# DA14580_QFN40.net
KiCad netlist of a schematic drawn in EAGLE
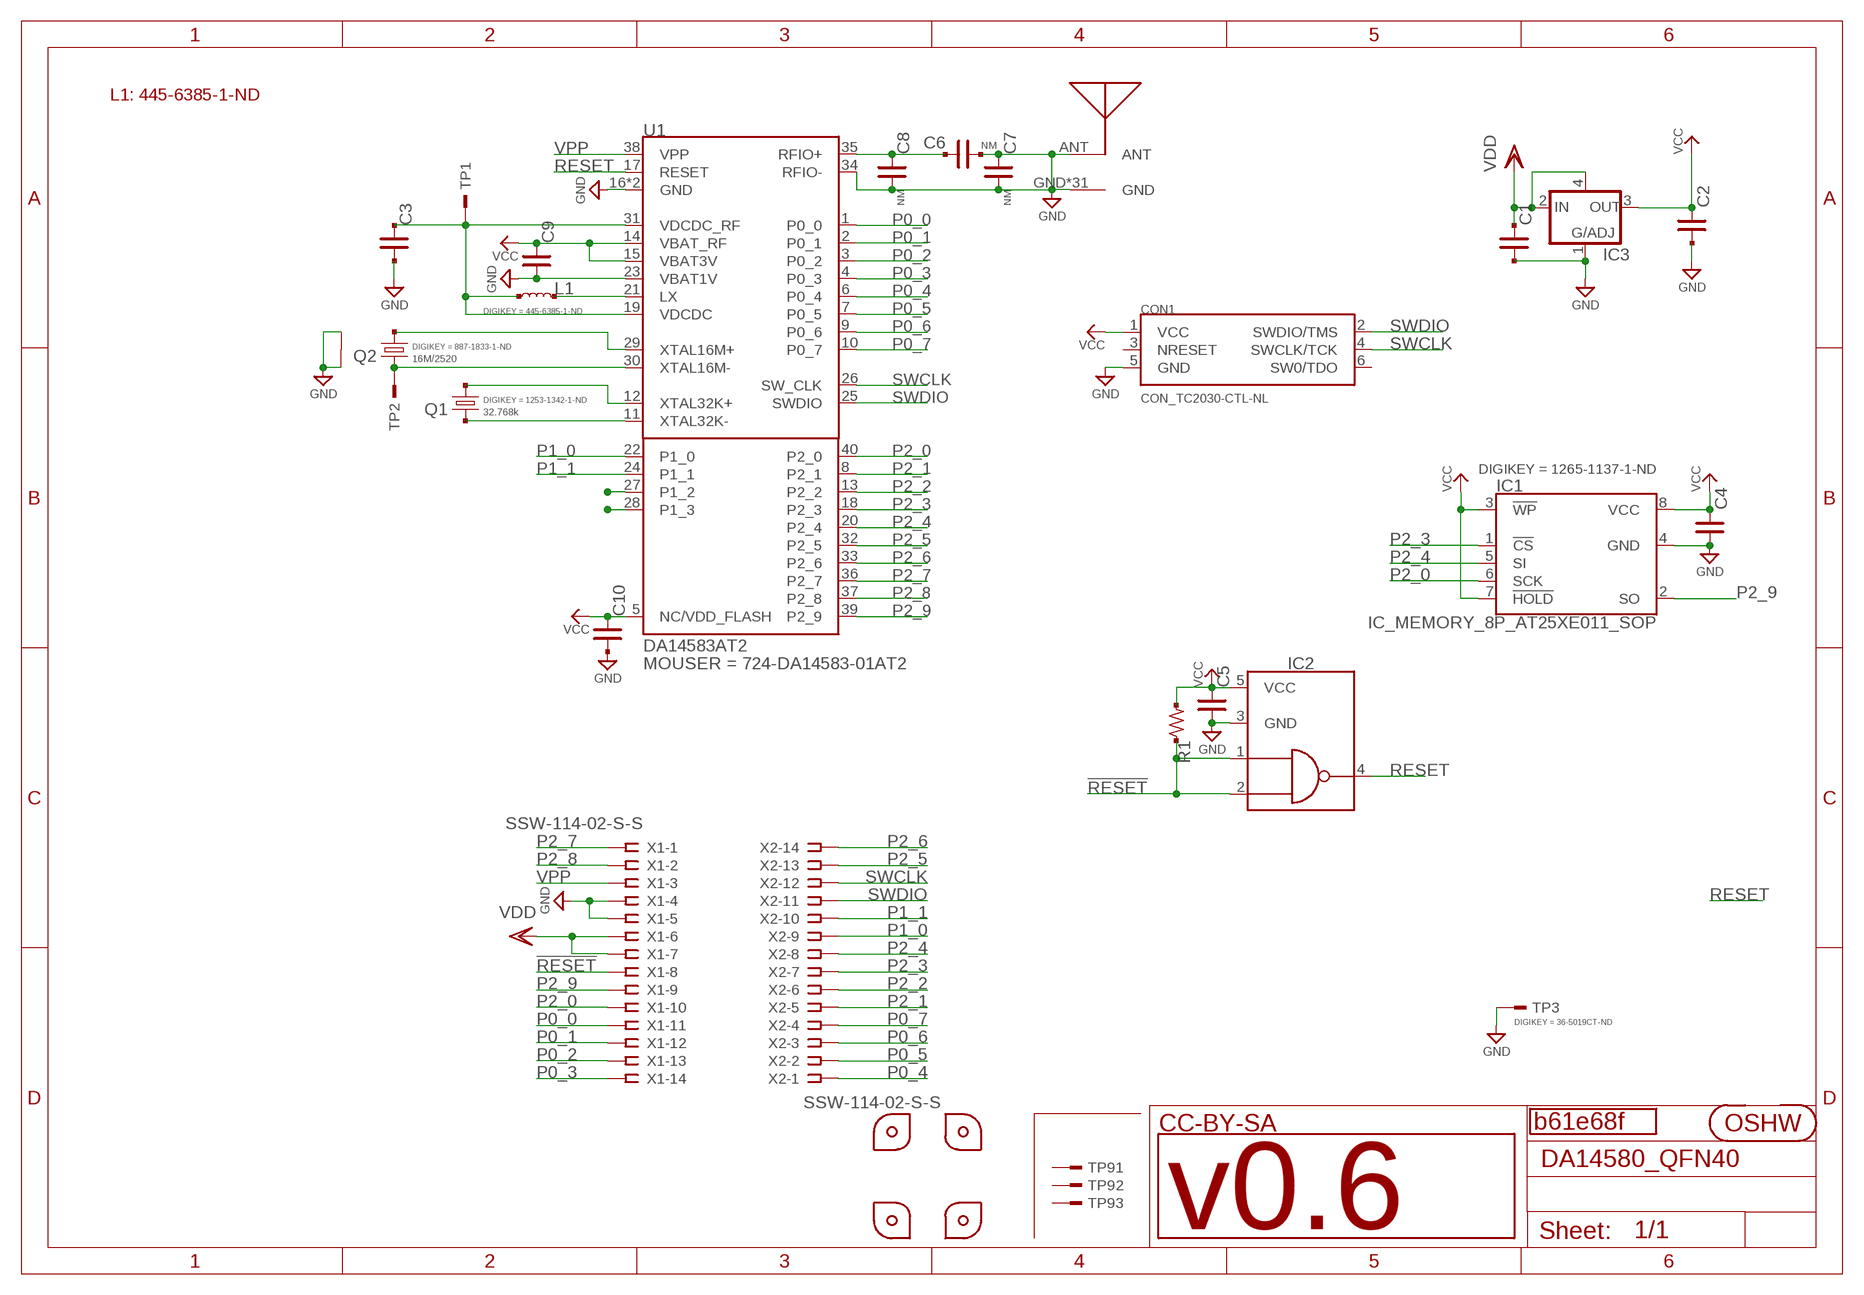
[diagram p0: schematic, sheet 1]

(export (version "E")
  (design (tool "Eeschema 10.0.6"))
  (components
    (comp (ref "C1")
      (value "C_SMD_1.0U_1005")
      (footprint "eagle-import:C0402")
      (libsource (lib "eagle-import") (part "C_SMD__10051.0U"))
    )
    (comp (ref "C2")
      (value "C_SMD_1.0U_1005")
      (footprint "eagle-import:C0402")
      (libsource (lib "eagle-import") (part "C_SMD__10051.0U"))
    )
    (comp (ref "C3")
      (value "C_SMD_1.0U_1005")
      (footprint "eagle-import:C0402")
      (libsource (lib "eagle-import") (part "C_SMD__10051.0U"))
    )
    (comp (ref "C4")
      (value "C_SMD_0.1U_1005")
      (footprint "eagle-import:C0402")
      (libsource (lib "eagle-import") (part "C_SMD__10050.1U"))
    )
    (comp (ref "C5")
      (value "C_SMD_0.1U_1005")
      (footprint "eagle-import:C0402")
      (libsource (lib "eagle-import") (part "C_SMD__10050.1U"))
    )
    (comp (ref "C6")
      (value "NM")
      (footprint "eagle-import:C0402")
      (libsource (lib "eagle-import") (part "C_SMD__100510P"))
    )
    (comp (ref "C7")
      (value "NM")
      (footprint "eagle-import:C0402")
      (libsource (lib "eagle-import") (part "C_SMD__1005"))
    )
    (comp (ref "C8")
      (value "NM")
      (footprint "eagle-import:C0402")
      (libsource (lib "eagle-import") (part "C_SMD__1005"))
    )
    (comp (ref "C9")
      (value "C_SMD_1.0U_1005")
      (footprint "eagle-import:C0402")
      (libsource (lib "eagle-import") (part "C_SMD__10051.0U"))
    )
    (comp (ref "C10")
      (value "C_SMD_0.1U_1005")
      (footprint "eagle-import:C0402")
      (libsource (lib "eagle-import") (part "C_SMD__10050.1U"))
    )
    (comp (ref "CON1")
      (value "CON_TC2030-CTL-NL")
      (footprint "eagle-import:CON_TC2030-IDC-NL")
      (libsource (lib "eagle-import") (part "CON_TC2030-CTL-NL"))
    )
    (comp (ref "GIT1")
      (value "b61e68f")
      (footprint "eagle-import:GIT-REVISION")
      (libsource (lib "eagle-import") (part "GIT-REVISION"))
    )
    (comp (ref "IC1")
      (value "IC_MEMORY_8P_AT25XE011_SOP")
      (footprint "eagle-import:IC_08_1.27_150MIL")
      (fields (field (name "DIGIKEY") "1265-1137-1-ND"))
      (libsource (lib "eagle-import") (part "IC_MEMORY_8P__SOPAT25XE011"))
    )
    (comp (ref "IC2")
      (value "74LVC1G00_DRL")
      (footprint "eagle-import:SOT50P160X120-5N")
      (libsource (lib "eagle-import") (part "741G00_DRLLVC"))
    )
    (comp (ref "IC3")
      (value "LDO4_3.3_SC82-AB")
      (footprint "eagle-import:SOT130P220X135-4N")
      (libsource (lib "eagle-import") (part "LDO4__SC82-AB3.3"))
    )
    (comp (ref "ICON1")
      (value "v0.6")
      (footprint "eagle-import:ICON_REVISION1.2")
      (libsource (lib "eagle-import") (part "ICON_REVISION_1.2"))
    )
    (comp (ref "L1")
      (value "INDUCTOR_2.2U_1608")
      (footprint "eagle-import:L_1608")
      (fields (field (name "DIGIKEY") "445-6385-1-ND"))
      (libsource (lib "eagle-import") (part "INDUCTOR__16082.2U"))
    )
    (comp (ref "P1")
      (value "PCB_CORNER_NH")
      (footprint "eagle-import:PCB_CORNER_NH")
      (libsource (lib "eagle-import") (part "PCB_CORNER_NH"))
    )
    (comp (ref "P2")
      (value "PCB_CORNER_NH")
      (footprint "eagle-import:PCB_CORNER_NH")
      (libsource (lib "eagle-import") (part "PCB_CORNER_NH"))
    )
    (comp (ref "P3")
      (value "PCB_CORNER")
      (footprint "eagle-import:PCB_CORNER")
      (libsource (lib "eagle-import") (part "PCB_CORNER"))
    )
    (comp (ref "P4")
      (value "PCB_CORNER")
      (footprint "eagle-import:PCB_CORNER")
      (libsource (lib "eagle-import") (part "PCB_CORNER"))
    )
    (comp (ref "Q1")
      (value "32.768k")
      (footprint "eagle-import:CR_2125")
      (fields (field (name "DIGIKEY") "1253-1342-1-ND"))
      (libsource (lib "eagle-import") (part "CRYSTAL2__201232.768K"))
    )
    (comp (ref "Q2")
      (value "16M/2520")
      (footprint "eagle-import:CLOCK_2520")
      (fields (field (name "DIGIKEY") "887-1833-1-ND"))
      (libsource (lib "eagle-import") (part "CRYSTAL4__252016M"))
    )
    (comp (ref "R1")
      (value "R_US_10K_1005")
      (footprint "eagle-import:C0402")
      (libsource (lib "eagle-import") (part "R_US__100510K"))
    )
    (comp (ref "TP1")
      (value "TESTPAD")
      (footprint "eagle-import:TP06RECT")
      (libsource (lib "eagle-import") (part "TESTPAD"))
    )
    (comp (ref "TP2")
      (value "TESTPAD")
      (footprint "eagle-import:TP06RECT")
      (libsource (lib "eagle-import") (part "TESTPAD"))
    )
    (comp (ref "TP3")
      (value "TESTPAD_4020")
      (footprint "eagle-import:TP_4020")
      (fields (field (name "DIGIKEY") "36-5019CT-ND"))
      (libsource (lib "eagle-import") (part "TESTPAD_4020"))
    )
    (comp (ref "TP91")
      (value "TESTPAD_F")
      (footprint "eagle-import:FIDUCIAL")
      (libsource (lib "eagle-import") (part "TESTPAD_F"))
    )
    (comp (ref "TP92")
      (value "TESTPAD_F")
      (footprint "eagle-import:FIDUCIAL")
      (libsource (lib "eagle-import") (part "TESTPAD_F"))
    )
    (comp (ref "TP93")
      (value "TESTPAD_F")
      (footprint "eagle-import:FIDUCIAL")
      (libsource (lib "eagle-import") (part "TESTPAD_F"))
    )
    (comp (ref "U$1")
      (value "ANT_IFA")
      (footprint "eagle-import:ANT_IFA_V2")
      (libsource (lib "eagle-import") (part "ANT_IFA"))
    )
    (comp (ref "U$2")
      (value "ICON_OSHW")
      (footprint "eagle-import:ICON_OSHW")
      (libsource (lib "eagle-import") (part "ICON_OSHW"))
    )
    (comp (ref "U1")
      (value "DA14583AT2")
      (footprint "eagle-import:QFN40_0.4P5.0X5.0")
      (fields (field (name "MOUSER") "724-DA14583-01AT2"))
      (libsource (lib "eagle-import") (part "DA1458AT23"))
    )
    (comp (ref "X1")
      (value "SSW-114-02-S-S")
      (footprint "eagle-import:SSW-114-02-S-S")
      (libsource (lib "eagle-import") (part "SSW-114-02-S-S"))
    )
    (comp (ref "X2")
      (value "SSW-114-02-S-S")
      (footprint "eagle-import:SSW-114-02-S-S")
      (libsource (lib "eagle-import") (part "SSW-114-02-S-S"))
    )
  )
  (nets
    (net (code "1") (name "/P0_0") (class "Default")
      (node (ref "U1") (pin "1") (pinfunction "P0_0_1") (pintype "bidirectional"))
      (node (ref "X1") (pin "11") (pinfunction "1_11") (pintype "passive"))
    )
    (net (code "2") (name "/P0_1") (class "Default")
      (node (ref "U1") (pin "2") (pinfunction "P0_1_2") (pintype "bidirectional"))
      (node (ref "X1") (pin "12") (pinfunction "1_12") (pintype "passive"))
    )
    (net (code "3") (name "/P0_2") (class "Default")
      (node (ref "U1") (pin "3") (pinfunction "P0_2_3") (pintype "bidirectional"))
      (node (ref "X1") (pin "13") (pinfunction "1_13") (pintype "passive"))
    )
    (net (code "4") (name "/P0_3") (class "Default")
      (node (ref "U1") (pin "4") (pinfunction "P0_3_4") (pintype "bidirectional"))
      (node (ref "X1") (pin "14") (pinfunction "1_14") (pintype "passive"))
    )
    (net (code "5") (name "/P0_4") (class "Default")
      (node (ref "U1") (pin "6") (pinfunction "P0_4_6") (pintype "bidirectional"))
      (node (ref "X2") (pin "1") (pinfunction "1_1") (pintype "passive"))
    )
    (net (code "6") (name "/P0_5") (class "Default")
      (node (ref "U1") (pin "7") (pinfunction "P0_5_7") (pintype "bidirectional"))
      (node (ref "X2") (pin "2") (pinfunction "1_2") (pintype "passive"))
    )
    (net (code "7") (name "/P0_6") (class "Default")
      (node (ref "U1") (pin "9") (pinfunction "P0_6_9") (pintype "bidirectional"))
      (node (ref "X2") (pin "3") (pinfunction "1_3") (pintype "passive"))
    )
    (net (code "8") (name "/P0_7") (class "Default")
      (node (ref "U1") (pin "10") (pinfunction "P0_7_10") (pintype "bidirectional"))
      (node (ref "X2") (pin "4") (pinfunction "1_4") (pintype "passive"))
    )
    (net (code "9") (name "/P1_0") (class "Default")
      (node (ref "U1") (pin "22") (pinfunction "P1_0_22") (pintype "bidirectional"))
      (node (ref "X2") (pin "9") (pinfunction "1_9") (pintype "passive"))
    )
    (net (code "10") (name "/P1_1") (class "Default")
      (node (ref "U1") (pin "24") (pinfunction "P1_1_24") (pintype "bidirectional"))
      (node (ref "X2") (pin "10") (pinfunction "1_10") (pintype "passive"))
    )
    (net (code "11") (name "/P2_0") (class "Default")
      (node (ref "IC1") (pin "6") (pinfunction "SCK_6") (pintype "input"))
      (node (ref "U1") (pin "40") (pinfunction "P2_0_40") (pintype "bidirectional"))
      (node (ref "X1") (pin "10") (pinfunction "1_10") (pintype "passive"))
    )
    (net (code "12") (name "/P2_1") (class "Default")
      (node (ref "U1") (pin "8") (pinfunction "P2_1_8") (pintype "bidirectional"))
      (node (ref "X2") (pin "5") (pinfunction "1_5") (pintype "passive"))
    )
    (net (code "13") (name "/P2_2") (class "Default")
      (node (ref "U1") (pin "13") (pinfunction "P2_2_13") (pintype "bidirectional"))
      (node (ref "X2") (pin "6") (pinfunction "1_6") (pintype "passive"))
    )
    (net (code "14") (name "/P2_3") (class "Default")
      (node (ref "IC1") (pin "1") (pinfunction "~{CS}_1") (pintype "input"))
      (node (ref "U1") (pin "18") (pinfunction "P2_3_18") (pintype "bidirectional"))
      (node (ref "X2") (pin "7") (pinfunction "1_7") (pintype "passive"))
    )
    (net (code "15") (name "/P2_4") (class "Default")
      (node (ref "IC1") (pin "5") (pinfunction "SI_5") (pintype "input"))
      (node (ref "U1") (pin "20") (pinfunction "P2_4_20") (pintype "bidirectional"))
      (node (ref "X2") (pin "8") (pinfunction "1_8") (pintype "passive"))
    )
    (net (code "16") (name "/P2_5") (class "Default")
      (node (ref "U1") (pin "32") (pinfunction "P2_5_32") (pintype "bidirectional"))
      (node (ref "X2") (pin "13") (pinfunction "1_13") (pintype "passive"))
    )
    (net (code "17") (name "/P2_6") (class "Default")
      (node (ref "U1") (pin "33") (pinfunction "P2_6_33") (pintype "bidirectional"))
      (node (ref "X2") (pin "14") (pinfunction "1_14") (pintype "passive"))
    )
    (net (code "18") (name "/P2_7") (class "Default")
      (node (ref "U1") (pin "36") (pinfunction "P2_7_36") (pintype "bidirectional"))
      (node (ref "X1") (pin "1") (pinfunction "1_1") (pintype "passive"))
    )
    (net (code "19") (name "/P2_8") (class "Default")
      (node (ref "U1") (pin "37") (pinfunction "P2_8_37") (pintype "bidirectional"))
      (node (ref "X1") (pin "2") (pinfunction "1_2") (pintype "passive"))
    )
    (net (code "20") (name "/P2_9") (class "Default")
      (node (ref "IC1") (pin "2") (pinfunction "SO_2") (pintype "output"))
      (node (ref "U1") (pin "39") (pinfunction "P2_9_39") (pintype "bidirectional"))
      (node (ref "X1") (pin "9") (pinfunction "1_9") (pintype "passive"))
    )
    (net (code "21") (name "/RESET") (class "Default")
      (node (ref "IC2") (pin "4") (pinfunction "1Y_4") (pintype "output"))
      (node (ref "U1") (pin "17") (pinfunction "RESET_17") (pintype "bidirectional"))
    )
    (net (code "22") (name "/SWCLK") (class "Default")
      (node (ref "CON1") (pin "4") (pinfunction "SWCLK/TCK_4") (pintype "bidirectional"))
      (node (ref "U1") (pin "26") (pinfunction "SW_CLK_26") (pintype "bidirectional"))
      (node (ref "X2") (pin "12") (pinfunction "1_12") (pintype "passive"))
    )
    (net (code "23") (name "/SWDIO") (class "Default")
      (node (ref "CON1") (pin "2") (pinfunction "SWDIO/TMS_2") (pintype "bidirectional"))
      (node (ref "U1") (pin "25") (pinfunction "SWDIO_25") (pintype "bidirectional"))
      (node (ref "X2") (pin "11") (pinfunction "1_11") (pintype "passive"))
    )
    (net (code "24") (name "/VPP") (class "Default")
      (node (ref "U1") (pin "38") (pinfunction "VPP_38") (pintype "power_in"))
      (node (ref "X1") (pin "3") (pinfunction "1_3") (pintype "passive"))
    )
    (net (code "25") (name "/~{RESET}") (class "Default")
      (node (ref "IC2") (pin "1") (pinfunction "1A_1") (pintype "input"))
      (node (ref "IC2") (pin "2") (pinfunction "1B_2") (pintype "input"))
      (node (ref "R1") (pin "1") (pinfunction "1_1") (pintype "passive"))
      (node (ref "X1") (pin "8") (pinfunction "1_8") (pintype "passive"))
    )
    (net (code "26") (name "GND") (class "Default")
      (node (ref "C1") (pin "2") (pinfunction "2_2") (pintype "passive"))
      (node (ref "C10") (pin "2") (pinfunction "2_2") (pintype "passive"))
      (node (ref "C2") (pin "2") (pinfunction "2_2") (pintype "passive"))
      (node (ref "C3") (pin "2") (pinfunction "2_2") (pintype "passive"))
      (node (ref "C4") (pin "2") (pinfunction "2_2") (pintype "passive"))
      (node (ref "C5") (pin "2") (pinfunction "2_2") (pintype "passive"))
      (node (ref "C6") (pin "2") (pinfunction "2_2") (pintype "passive"))
      (node (ref "C7") (pin "1") (pinfunction "1_1") (pintype "passive"))
      (node (ref "C7") (pin "2") (pinfunction "2_2") (pintype "passive"))
      (node (ref "C8") (pin "2") (pinfunction "2_2") (pintype "passive"))
      (node (ref "C9") (pin "2") (pinfunction "2_2") (pintype "passive"))
      (node (ref "CON1") (pin "5") (pinfunction "GND_5") (pintype "bidirectional"))
      (node (ref "IC1") (pin "4") (pinfunction "GND_4") (pintype "power_in"))
      (node (ref "IC2") (pin "3") (pinfunction "GND_3") (pintype "power_in"))
      (node (ref "IC3") (pin "1") (pinfunction "ADJ_1") (pintype "power_in"))
      (node (ref "Q2") (pin "2") (pinfunction "P$1_2") (pintype "bidirectional"))
      (node (ref "Q2") (pin "4") (pinfunction "P$2_4") (pintype "bidirectional"))
      (node (ref "TP3") (pin "TP") (pinfunction "1_TP") (pintype "passive"))
      (node (ref "U$1") (pin "ANT") (pinfunction "ANT_ANT") (pintype "bidirectional"))
      (node (ref "U$1") (pin "GND") (pinfunction "GND_GND") (pintype "bidirectional"))
      (node (ref "U$1") (pin "GND@1") (pinfunction "GND_GND@1") (pintype "bidirectional"))
      (node (ref "U$1") (pin "GND@10") (pinfunction "GND_GND@10") (pintype "bidirectional"))
      (node (ref "U$1") (pin "GND@11") (pinfunction "GND_GND@11") (pintype "bidirectional"))
      (node (ref "U$1") (pin "GND@12") (pinfunction "GND_GND@12") (pintype "bidirectional"))
      (node (ref "U$1") (pin "GND@13") (pinfunction "GND_GND@13") (pintype "bidirectional"))
      (node (ref "U$1") (pin "GND@14") (pinfunction "GND_GND@14") (pintype "bidirectional"))
      (node (ref "U$1") (pin "GND@15") (pinfunction "GND_GND@15") (pintype "bidirectional"))
      (node (ref "U$1") (pin "GND@16") (pinfunction "GND_GND@16") (pintype "bidirectional"))
      (node (ref "U$1") (pin "GND@17") (pinfunction "GND_GND@17") (pintype "bidirectional"))
      (node (ref "U$1") (pin "GND@18") (pinfunction "GND_GND@18") (pintype "bidirectional"))
      (node (ref "U$1") (pin "GND@19") (pinfunction "GND_GND@19") (pintype "bidirectional"))
      (node (ref "U$1") (pin "GND@2") (pinfunction "GND_GND@2") (pintype "bidirectional"))
      (node (ref "U$1") (pin "GND@20") (pinfunction "GND_GND@20") (pintype "bidirectional"))
      (node (ref "U$1") (pin "GND@21") (pinfunction "GND_GND@21") (pintype "bidirectional"))
      (node (ref "U$1") (pin "GND@22") (pinfunction "GND_GND@22") (pintype "bidirectional"))
      (node (ref "U$1") (pin "GND@23") (pinfunction "GND_GND@23") (pintype "bidirectional"))
      (node (ref "U$1") (pin "GND@24") (pinfunction "GND_GND@24") (pintype "bidirectional"))
      (node (ref "U$1") (pin "GND@25") (pinfunction "GND_GND@25") (pintype "bidirectional"))
      (node (ref "U$1") (pin "GND@26") (pinfunction "GND_GND@26") (pintype "bidirectional"))
      (node (ref "U$1") (pin "GND@27") (pinfunction "GND_GND@27") (pintype "bidirectional"))
      (node (ref "U$1") (pin "GND@28") (pinfunction "GND_GND@28") (pintype "bidirectional"))
      (node (ref "U$1") (pin "GND@29") (pinfunction "GND_GND@29") (pintype "bidirectional"))
      (node (ref "U$1") (pin "GND@3") (pinfunction "GND_GND@3") (pintype "bidirectional"))
      (node (ref "U$1") (pin "GND@30") (pinfunction "GND_GND@30") (pintype "bidirectional"))
      (node (ref "U$1") (pin "GND@4") (pinfunction "GND_GND@4") (pintype "bidirectional"))
      (node (ref "U$1") (pin "GND@5") (pinfunction "GND_GND@5") (pintype "bidirectional"))
      (node (ref "U$1") (pin "GND@6") (pinfunction "GND_GND@6") (pintype "bidirectional"))
      (node (ref "U$1") (pin "GND@7") (pinfunction "GND_GND@7") (pintype "bidirectional"))
      (node (ref "U$1") (pin "GND@8") (pinfunction "GND_GND@8") (pintype "bidirectional"))
      (node (ref "U$1") (pin "GND@9") (pinfunction "GND_GND@9") (pintype "bidirectional"))
      (node (ref "U1") (pin "16") (pinfunction "GND_16") (pintype "power_in"))
      (node (ref "U1") (pin "23") (pinfunction "VBAT1V_23") (pintype "power_in"))
      (node (ref "U1") (pin "34") (pinfunction "RFIO-_34") (pintype "bidirectional"))
      (node (ref "U1") (pin "BP") (pinfunction "GND_BP") (pintype "power_in"))
      (node (ref "X1") (pin "4") (pinfunction "1_4") (pintype "passive"))
      (node (ref "X1") (pin "5") (pinfunction "1_5") (pintype "passive"))
    )
    (net (code "27") (name "Net-(Q2-2)") (class "Default")
      (node (ref "Q2") (pin "3") (pinfunction "2_3") (pintype "passive"))
      (node (ref "TP2") (pin "TP") (pinfunction "1_TP") (pintype "passive"))
      (node (ref "U1") (pin "30") (pinfunction "XTAL16M-_30") (pintype "bidirectional"))
    )
    (net (code "28") (name "Net-(TP1-1)") (class "Default")
      (node (ref "C3") (pin "1") (pinfunction "1_1") (pintype "passive"))
      (node (ref "L1") (pin "1") (pinfunction "1_1") (pintype "passive"))
      (node (ref "TP1") (pin "TP") (pinfunction "1_TP") (pintype "passive"))
      (node (ref "U1") (pin "19") (pinfunction "VDCDC_19") (pintype "power_in"))
      (node (ref "U1") (pin "31") (pinfunction "VDCDC_RF_31") (pintype "power_in"))
    )
    (net (code "29") (name "Net-(U1-LX)") (class "Default")
      (node (ref "L1") (pin "2") (pinfunction "2_2") (pintype "passive"))
      (node (ref "U1") (pin "21") (pinfunction "LX_21") (pintype "bidirectional"))
    )
    (net (code "30") (name "Net-(U1-RFIO+)") (class "Default")
      (node (ref "C6") (pin "1") (pinfunction "1_1") (pintype "passive"))
      (node (ref "C8") (pin "1") (pinfunction "1_1") (pintype "passive"))
      (node (ref "U1") (pin "35") (pinfunction "RFIO+_35") (pintype "bidirectional"))
    )
    (net (code "31") (name "Net-(U1-XTAL16M+)") (class "Default")
      (node (ref "Q2") (pin "1") (pinfunction "1_1") (pintype "passive"))
      (node (ref "U1") (pin "29") (pinfunction "XTAL16M+_29") (pintype "bidirectional"))
    )
    (net (code "32") (name "Net-(U1-XTAL32K+)") (class "Default")
      (node (ref "Q1") (pin "1") (pinfunction "1_1") (pintype "passive"))
      (node (ref "U1") (pin "12") (pinfunction "XTAL32K+_12") (pintype "bidirectional"))
    )
    (net (code "33") (name "Net-(U1-XTAL32K-)") (class "Default")
      (node (ref "Q1") (pin "2") (pinfunction "2_2") (pintype "passive"))
      (node (ref "U1") (pin "11") (pinfunction "XTAL32K-_11") (pintype "bidirectional"))
    )
    (net (code "34") (name "VCC") (class "Default")
      (node (ref "C10") (pin "1") (pinfunction "1_1") (pintype "passive"))
      (node (ref "C2") (pin "1") (pinfunction "1_1") (pintype "passive"))
      (node (ref "C4") (pin "1") (pinfunction "1_1") (pintype "passive"))
      (node (ref "C5") (pin "1") (pinfunction "1_1") (pintype "passive"))
      (node (ref "C9") (pin "1") (pinfunction "1_1") (pintype "passive"))
      (node (ref "CON1") (pin "1") (pinfunction "VCC_1") (pintype "bidirectional"))
      (node (ref "IC1") (pin "3") (pinfunction "~{WP}_3") (pintype "input"))
      (node (ref "IC1") (pin "7") (pinfunction "~{HOLD}_7") (pintype "input"))
      (node (ref "IC1") (pin "8") (pinfunction "VCC_8") (pintype "power_in"))
      (node (ref "IC2") (pin "5") (pinfunction "VCC_5") (pintype "power_in"))
      (node (ref "IC3") (pin "3") (pinfunction "OUT_3") (pintype "power_in"))
      (node (ref "R1") (pin "2") (pinfunction "2_2") (pintype "passive"))
      (node (ref "U1") (pin "14") (pinfunction "VBAT_RF_14") (pintype "power_in"))
      (node (ref "U1") (pin "15") (pinfunction "VBAT3V_15") (pintype "power_in"))
      (node (ref "U1") (pin "5") (pinfunction "NC/VDD_FLASH_5") (pintype "power_in"))
    )
    (net (code "35") (name "VDD") (class "Default")
      (node (ref "C1") (pin "1") (pinfunction "1_1") (pintype "passive"))
      (node (ref "IC3") (pin "2") (pinfunction "IN_2") (pintype "power_in"))
      (node (ref "IC3") (pin "4") (pinfunction "OUT/EN/NC_4") (pintype "tri_state"))
      (node (ref "X1") (pin "6") (pinfunction "1_6") (pintype "passive"))
      (node (ref "X1") (pin "7") (pinfunction "1_7") (pintype "passive"))
    )
    (net (code "36") (name "unconnected-(CON1-NRESET-Pad3)") (class "Default")
      (node (ref "CON1") (pin "3") (pinfunction "NRESET_3") (pintype "bidirectional"))
    )
    (net (code "37") (name "unconnected-(CON1-SW0{slash}TDO-Pad6)") (class "Default")
      (node (ref "CON1") (pin "6") (pinfunction "SW0/TDO_6") (pintype "bidirectional"))
    )
    (net (code "38") (name "unconnected-(TP91-1-PadTP)") (class "Default")
      (node (ref "TP91") (pin "TP") (pinfunction "1_TP") (pintype "passive"))
    )
    (net (code "39") (name "unconnected-(TP92-1-PadTP)") (class "Default")
      (node (ref "TP92") (pin "TP") (pinfunction "1_TP") (pintype "passive"))
    )
    (net (code "40") (name "unconnected-(TP93-1-PadTP)") (class "Default")
      (node (ref "TP93") (pin "TP") (pinfunction "1_TP") (pintype "passive"))
    )
    (net (code "41") (name "unconnected-(U1-P1_2-Pad27)") (class "Default")
      (node (ref "U1") (pin "27") (pinfunction "P1_2_27") (pintype "bidirectional"))
    )
    (net (code "42") (name "unconnected-(U1-P1_3-Pad28)") (class "Default")
      (node (ref "U1") (pin "28") (pinfunction "P1_3_28") (pintype "bidirectional"))
    )
  )
)
